# Storage.net
KiCad netlist of a schematic drawn in Altium Designer
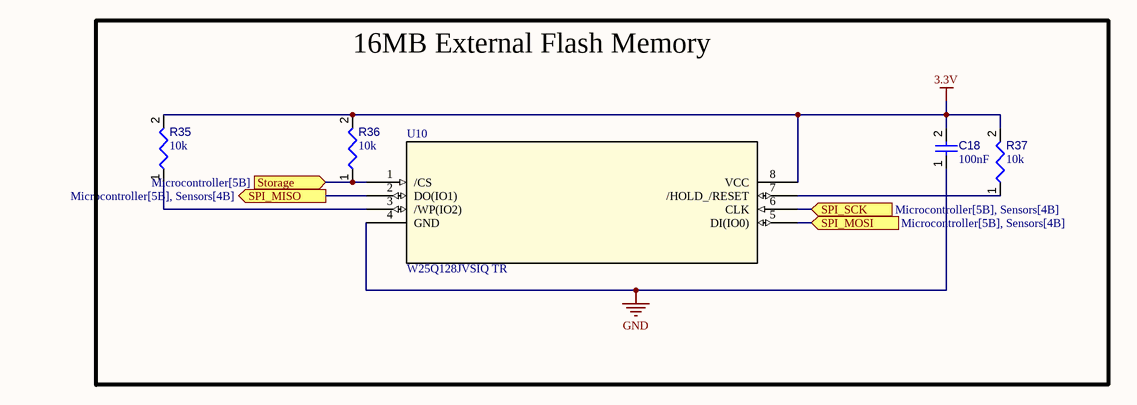
[diagram p0: Storage.SchDoc]

(export (version "E")
  (design (tool "Eeschema 10.0.6"))
  (components
    (comp (ref "C18")
      (value "100nF")
      (footprint "FP-GCJ188-0_2-IPC_C")
      (description "16V 100nF X7R ±10% 0603 Multilayer Ceramic Capacitors MLCC - SMD/SMT ROHS")
      (fields (field (name "TOLERANCE") "10%") (field (name "Comment") "GCJ188R71C104KA01D"))
      (libsource (lib "Buddhi Rashmika") (part "CAP-NP-2"))
    )
    (comp (ref "R35")
      (value "10k")
      (footprint "RESC2013X50X35ML15T15")
      (description "Chip Resistor, 10 KOhm, +/- 1%, 125 mW, -55 to 155 degC, 0805 (2012 Metric)")
      (fields (field (name "TOLERANCE") "1%") (field (name "POWER") "125mW"))
      (libsource (lib "Buddhi Rashmika") (part "RES-2"))
    )
    (comp (ref "R36")
      (value "10k")
      (footprint "RESC2013X50X35ML15T15")
      (description "Chip Resistor, 10 KOhm, +/- 1%, 125 mW, -55 to 155 degC, 0805 (2012 Metric)")
      (fields (field (name "TOLERANCE") "1%") (field (name "POWER") "125mW"))
      (libsource (lib "Buddhi Rashmika") (part "RES-2"))
    )
    (comp (ref "R37")
      (value "10k")
      (footprint "RESC2013X50X35ML15T15")
      (description "Chip Resistor, 10 KOhm, +/- 1%, 125 mW, -55 to 155 degC, 0805 (2012 Metric)")
      (fields (field (name "TOLERANCE") "1%") (field (name "POWER") "125mW"))
      (libsource (lib "Buddhi Rashmika") (part "RES-2"))
    )
    (comp (ref "U10")
      (value "W25Q128JVSIQ TR")
      (footprint "SOIC_208MIL_WIN")
      (description "Description")
      (fields (field (name "COPYRIGHT") "Copyright (C) 2025 Ultra Librarian. All rights reserved."))
      (libsource (lib "Schlib1") (part "W25Q128JVSIQ TR"))
    )
  )
  (nets
    (net (code "1") (name "/SPI_MISO") (class "Default")
      (node (ref "U10") (pin "2") (pinfunction "DO(IO1)_2") (pintype "bidirectional"))
    )
    (net (code "2") (name "/SPI_MOSI") (class "Default")
      (node (ref "U10") (pin "5") (pinfunction "DI(IO0)_5") (pintype "bidirectional"))
    )
    (net (code "3") (name "/SPI_SCK") (class "Default")
      (node (ref "U10") (pin "6") (pinfunction "CLK_6") (pintype "input"))
    )
    (net (code "4") (name "/Storage") (class "Default")
      (node (ref "R36") (pin "1") (pinfunction "1_1") (pintype "passive"))
      (node (ref "U10") (pin "1") (pinfunction "/CS_1") (pintype "input"))
    )
    (net (code "5") (name "3.3V") (class "Default")
      (node (ref "C18") (pin "2") (pinfunction "2_2") (pintype "passive"))
      (node (ref "R35") (pin "2") (pinfunction "2_2") (pintype "passive"))
      (node (ref "R36") (pin "2") (pinfunction "2_2") (pintype "passive"))
      (node (ref "R37") (pin "2") (pinfunction "2_2") (pintype "passive"))
      (node (ref "U10") (pin "8") (pinfunction "VCC_8") (pintype "power_in"))
    )
    (net (code "6") (name "GND") (class "Default")
      (node (ref "C18") (pin "1") (pinfunction "1_1") (pintype "passive"))
      (node (ref "U10") (pin "4") (pinfunction "GND_4") (pintype "power_in"))
    )
    (net (code "7") (name "Net-(U10-{slash}HOLD_{slash}RESET)") (class "Default")
      (node (ref "R37") (pin "1") (pinfunction "1_1") (pintype "passive"))
      (node (ref "U10") (pin "7") (pinfunction "/HOLD_/RESET_7") (pintype "bidirectional"))
    )
    (net (code "8") (name "Net-(U10-{slash}WP(IO2))") (class "Default")
      (node (ref "R35") (pin "1") (pinfunction "1_1") (pintype "passive"))
      (node (ref "U10") (pin "3") (pinfunction "/WP(IO2)_3") (pintype "bidirectional"))
    )
  )
)
